# dsau-micro-zed.net
KiCad netlist of a schematic drawn in Altium Designer
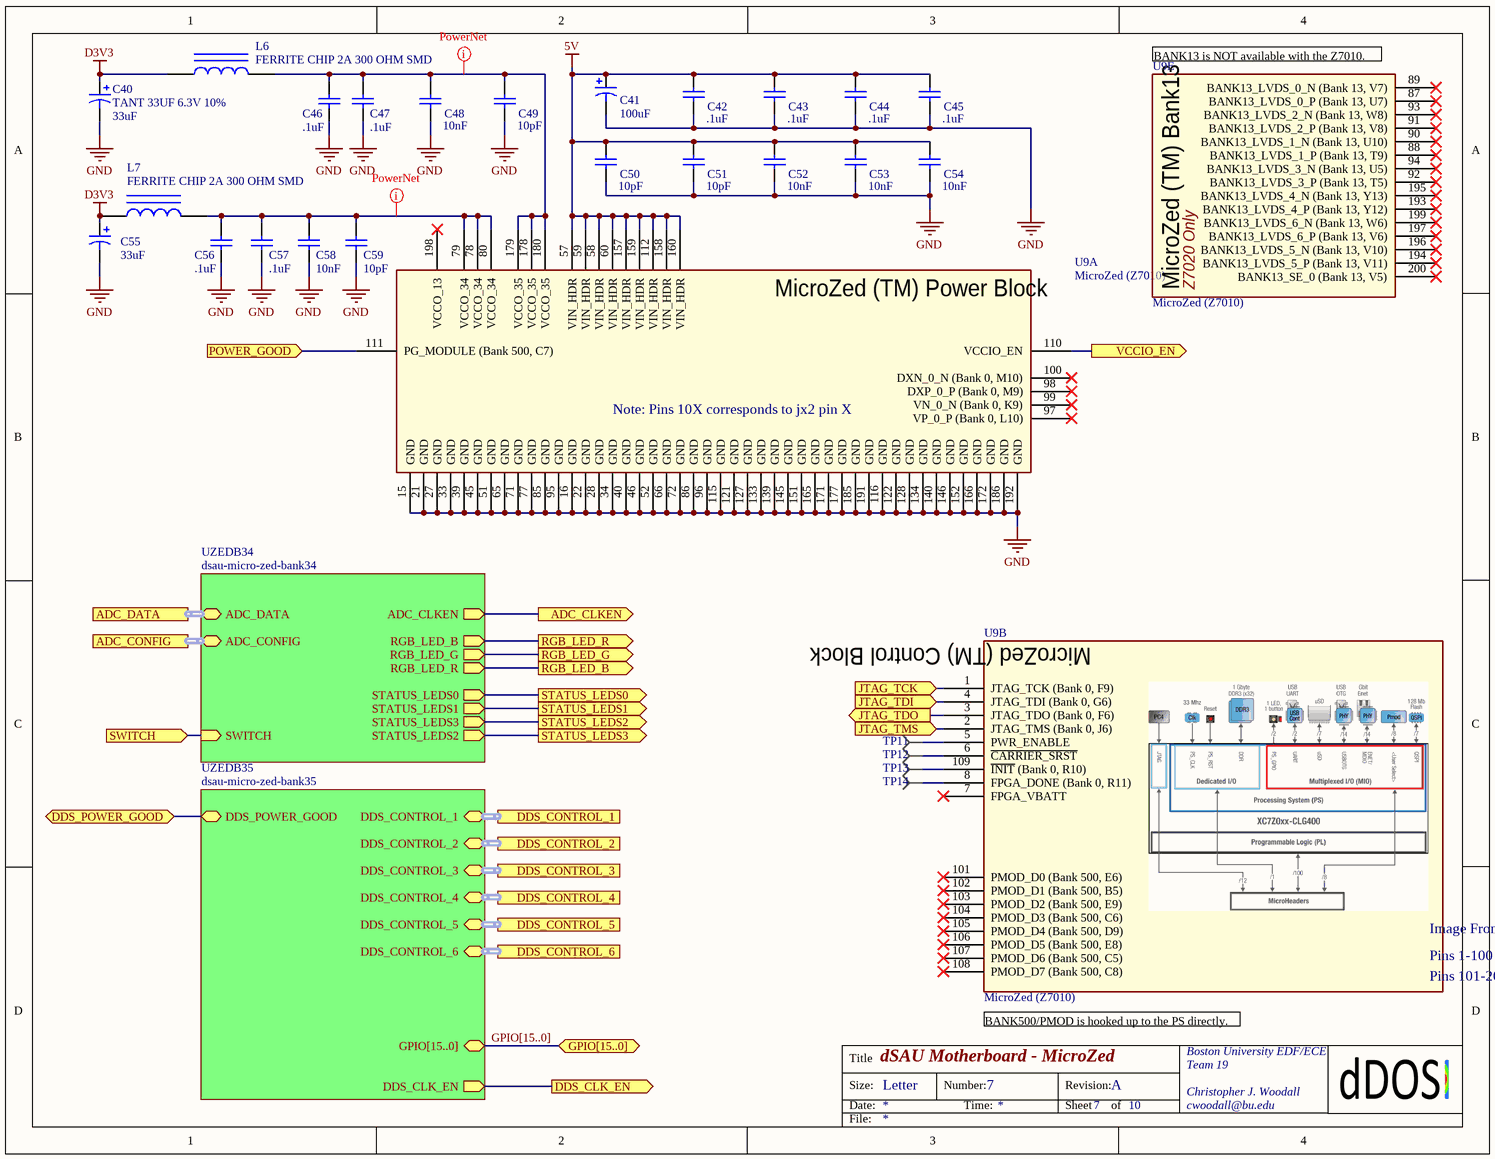
[diagram p0: dsau-micro-zed.SchDoc]

(export (version "E")
  (design (tool "Eeschema 10.0.6"))
  (components
    (comp (ref "C40")
      (value "TANT 33UF 6.3V 10%")
      (footprint "CAPC2012L")
      (description "Polarized Capacitor (Surface Mount)")
      (fields
        (field (name "ALTIUM_VALUE") "33uF")
        (field (name "MANUFACTURER") "AVX Corporation")
        (field (name "MANUFACTURER PART NUMBER") "TPSA336K006R0600")
        (field (name "PUBLISHER") "Altium Limited")
      )
      (libsource (lib "") (part "Cap Pol3_1"))
    )
    (comp (ref "C41")
      (value "100uF")
      (footprint "CAPPOL3216")
      (description "Polarized Capacitor (Surface Mount)")
      (fields
        (field (name "MANUFACTURER") "Vishay Sprague")
        (field (name "MANUFACTURER PART NUMBER") "TL8A0107M010C")
        (field (name "PUBLISHER") "Altium Limited")
      )
      (libsource (lib "Miscellaneous Devices") (part "Cap Pol3"))
    )
    (comp (ref "C42")
      (value ".1uF")
      (footprint "CAPC1608L")
      (description "Capacitor")
      (fields
        (field (name "MANUFACTURER") "Yageo")
        (field (name "MANUFACTURER PART NUMBER") "CC0603ZRY5V9BB104")
        (field (name "PUBLISHER") "Altium Limited")
      )
      (libsource (lib "Miscellaneous Devices") (part "Cap"))
    )
    (comp (ref "C43")
      (value ".1uF")
      (footprint "CAPC1608L")
      (description "Capacitor")
      (fields
        (field (name "MANUFACTURER") "Yageo")
        (field (name "MANUFACTURER PART NUMBER") "CC0603ZRY5V9BB104")
        (field (name "PUBLISHER") "Altium Limited")
      )
      (libsource (lib "Miscellaneous Devices") (part "Cap"))
    )
    (comp (ref "C44")
      (value ".1uF")
      (footprint "CAPC1608L")
      (description "Capacitor")
      (fields
        (field (name "MANUFACTURER") "Yageo")
        (field (name "MANUFACTURER PART NUMBER") "CC0603ZRY5V9BB104")
        (field (name "PUBLISHER") "Altium Limited")
      )
      (libsource (lib "Miscellaneous Devices") (part "Cap"))
    )
    (comp (ref "C45")
      (value ".1uF")
      (footprint "CAPC1608L")
      (description "Capacitor")
      (fields
        (field (name "MANUFACTURER") "Yageo")
        (field (name "MANUFACTURER PART NUMBER") "CC0603ZRY5V9BB104")
        (field (name "PUBLISHER") "Altium Limited")
      )
      (libsource (lib "Miscellaneous Devices") (part "Cap"))
    )
    (comp (ref "C46")
      (value ".1uF")
      (footprint "CAPC1608L")
      (description "Capacitor")
      (fields
        (field (name "MANUFACTURER") "Yageo")
        (field (name "MANUFACTURER PART NUMBER") "CC0603ZRY5V9BB104")
        (field (name "PUBLISHER") "Altium Limited")
      )
      (libsource (lib "Miscellaneous Devices") (part "Cap"))
    )
    (comp (ref "C47")
      (value ".1uF")
      (footprint "CAPC1608L")
      (description "Capacitor")
      (fields
        (field (name "MANUFACTURER") "Yageo")
        (field (name "MANUFACTURER PART NUMBER") "CC0603ZRY5V9BB104")
        (field (name "PUBLISHER") "Altium Limited")
      )
      (libsource (lib "Miscellaneous Devices") (part "Cap"))
    )
    (comp (ref "C48")
      (value "10nF")
      (footprint "CAPC1608L")
      (description "Capacitor")
      (fields
        (field (name "MANUFACTURER") "Kemet")
        (field (name "MANUFACTURER PART NUMBER") "C0603C103K3GACTU")
        (field (name "PUBLISHER") "Altium Limited")
      )
      (libsource (lib "Miscellaneous Devices") (part "Cap"))
    )
    (comp (ref "C49")
      (value "10pF")
      (footprint "CAPC1608L")
      (description "Capacitor")
      (fields
        (field (name "MANUFACTURER") "Samsung Electro-Mechanics America, Inc")
        (field (name "MANUFACTURER PART NUMBER") "CL10C100JB8NCNC")
        (field (name "PUBLISHER") "Altium Limited")
      )
      (libsource (lib "Miscellaneous Devices") (part "Cap"))
    )
    (comp (ref "C50")
      (value "10pF")
      (footprint "CAPC1608L")
      (description "Capacitor")
      (fields
        (field (name "MANUFACTURER") "Samsung Electro-Mechanics America, Inc")
        (field (name "MANUFACTURER PART NUMBER") "CL10C100JB8NCNC")
        (field (name "PUBLISHER") "Altium Limited")
      )
      (libsource (lib "Miscellaneous Devices") (part "Cap"))
    )
    (comp (ref "C51")
      (value "10pF")
      (footprint "CAPC1608L")
      (description "Capacitor")
      (fields
        (field (name "MANUFACTURER") "Samsung Electro-Mechanics America, Inc")
        (field (name "MANUFACTURER PART NUMBER") "CL10C100JB8NCNC")
        (field (name "PUBLISHER") "Altium Limited")
      )
      (libsource (lib "Miscellaneous Devices") (part "Cap"))
    )
    (comp (ref "C52")
      (value "10nF")
      (footprint "CAPC1608L")
      (description "Capacitor")
      (fields
        (field (name "MANUFACTURER") "Kemet")
        (field (name "MANUFACTURER PART NUMBER") "C0603C103K3GACTU")
        (field (name "PUBLISHER") "Altium Limited")
      )
      (libsource (lib "Miscellaneous Devices") (part "Cap"))
    )
    (comp (ref "C53")
      (value "10nF")
      (footprint "CAPC1608L")
      (description "Capacitor")
      (fields
        (field (name "MANUFACTURER") "Kemet")
        (field (name "MANUFACTURER PART NUMBER") "C0603C103K3GACTU")
        (field (name "PUBLISHER") "Altium Limited")
      )
      (libsource (lib "Miscellaneous Devices") (part "Cap"))
    )
    (comp (ref "C54")
      (value "10nF")
      (footprint "CAPC1608L")
      (description "Capacitor")
      (fields
        (field (name "MANUFACTURER") "Kemet")
        (field (name "MANUFACTURER PART NUMBER") "C0603C103K3GACTU")
        (field (name "PUBLISHER") "Altium Limited")
      )
      (libsource (lib "Miscellaneous Devices") (part "Cap"))
    )
    (comp (ref "C55")
      (value "33uF")
      (footprint "CAPC2012L")
      (description "Polarized Capacitor (Surface Mount)")
      (fields
        (field (name "MANUFACTURER") "AVX Corporation")
        (field (name "MANUFACTURER PART NUMBER") "TPSA336K006R0600")
        (field (name "PUBLISHER") "Altium Limited")
      )
      (libsource (lib "") (part "Cap Pol3_1"))
    )
    (comp (ref "C56")
      (value ".1uF")
      (footprint "CAPC1608L")
      (description "Capacitor")
      (fields
        (field (name "MANUFACTURER") "Yageo")
        (field (name "MANUFACTURER PART NUMBER") "CC0603ZRY5V9BB104")
        (field (name "PUBLISHER") "Altium Limited")
      )
      (libsource (lib "Miscellaneous Devices") (part "Cap"))
    )
    (comp (ref "C57")
      (value ".1uF")
      (footprint "CAPC1608L")
      (description "Capacitor")
      (fields
        (field (name "MANUFACTURER") "Yageo")
        (field (name "MANUFACTURER PART NUMBER") "CC0603ZRY5V9BB104")
        (field (name "PUBLISHER") "Altium Limited")
      )
      (libsource (lib "Miscellaneous Devices") (part "Cap"))
    )
    (comp (ref "C58")
      (value "10nF")
      (footprint "CAPC1608L")
      (description "Capacitor")
      (fields
        (field (name "MANUFACTURER") "Kemet")
        (field (name "MANUFACTURER PART NUMBER") "C0603C103K3GACTU")
        (field (name "PUBLISHER") "Altium Limited")
      )
      (libsource (lib "Miscellaneous Devices") (part "Cap"))
    )
    (comp (ref "C59")
      (value "10pF")
      (footprint "CAPC1608L")
      (description "Capacitor")
      (fields
        (field (name "MANUFACTURER") "Samsung Electro-Mechanics America, Inc")
        (field (name "MANUFACTURER PART NUMBER") "CL10C100JB8NCNC")
        (field (name "PUBLISHER") "Altium Limited")
      )
      (libsource (lib "Miscellaneous Devices") (part "Cap"))
    )
    (comp (ref "L6")
      (value "FERRITE CHIP 2A 300 OHM SMD")
      (footprint "INDC1608L")
      (description "Magnetic-Core Inductor")
      (fields
        (field (name "MANUFACTURER") "Laird-Signal Integrity Products")
        (field (name "MANUFACTURER PART NUMBER") "MI0603L301R-10")
        (field (name "PUBLISHER") "Altium Limited")
      )
      (libsource (lib "Miscellaneous Devices") (part "Inductor Iron"))
    )
    (comp (ref "L7")
      (value "FERRITE CHIP 2A 300 OHM SMD")
      (footprint "INDC1608L")
      (description "Magnetic-Core Inductor")
      (fields
        (field (name "MANUFACTURER") "Laird-Signal Integrity Products")
        (field (name "MANUFACTURER PART NUMBER") "MI0603L301R-10")
        (field (name "PUBLISHER") "Altium Limited")
      )
      (libsource (lib "Miscellaneous Devices") (part "Inductor Iron"))
    )
    (comp (ref "TP11")
      (value "TESTPOINT_CW")
      (footprint "PIN1")
      (fields (field (name "MANUFACTURER") "Keystone") (field (name "MANUFACTURER PART NUMBER") "5000"))
      (libsource (lib "dsau-motherboard") (part "TESTPOINT_CW"))
    )
    (comp (ref "TP12")
      (value "TESTPOINT_CW")
      (footprint "PIN1")
      (fields (field (name "MANUFACTURER") "Keystone") (field (name "MANUFACTURER PART NUMBER") "5000"))
      (libsource (lib "dsau-motherboard") (part "TESTPOINT_CW"))
    )
    (comp (ref "TP13")
      (value "TESTPOINT_CW")
      (footprint "PIN1")
      (fields (field (name "MANUFACTURER") "Keystone") (field (name "MANUFACTURER PART NUMBER") "5000"))
      (libsource (lib "dsau-motherboard") (part "TESTPOINT_CW"))
    )
    (comp (ref "TP14")
      (value "TESTPOINT_CW")
      (footprint "PIN1")
      (fields (field (name "MANUFACTURER") "Keystone") (field (name "MANUFACTURER PART NUMBER") "5000"))
      (libsource (lib "dsau-motherboard") (part "TESTPOINT_CW"))
    )
    (comp (ref "U9")
      (value "MicroZed (Z7010)")
      (footprint "MicroZed_MatingSide")
      (fields
        (field (name "MANUFACTURER") "Avnet")
        (field (name "MANFACTURER PART NUMBER") "AES-Z7MB-7Z010-G")
      )
      (libsource (lib "dsau-motherboard") (part "MicroZed"))
    )
  )
  (nets
    (net (code "37") (name "/JTAG_TCK") (class "Default")
      (node (ref "U9") (pin "1") (pinfunction "JTAG_TCK_(Bank_0,_F9)_1") (pintype "passive"))
    )
    (net (code "38") (name "/JTAG_TDI") (class "Default")
      (node (ref "U9") (pin "4") (pinfunction "JTAG_TDI_(Bank_0,_G6)_4") (pintype "passive"))
    )
    (net (code "39") (name "/JTAG_TDO") (class "Default")
      (node (ref "U9") (pin "3") (pinfunction "JTAG_TDO_(Bank_0,_F6)_3") (pintype "passive"))
    )
    (net (code "40") (name "/JTAG_TMS") (class "Default")
      (node (ref "U9") (pin "2") (pinfunction "JTAG_TMS_(Bank_0,_J6)_2") (pintype "passive"))
    )
    (net (code "41") (name "/POWER_GOOD") (class "Default")
      (node (ref "U9") (pin "111") (pinfunction "PG_MODULE_(Bank_500,_C7)_111") (pintype "passive"))
    )
    (net (code "50") (name "/VCCIO_EN") (class "Default")
      (node (ref "U9") (pin "110") (pinfunction "VCCIO_EN_110") (pintype "passive"))
    )
    (net (code "51") (name "5V") (class "Default")
      (node (ref "C41") (pin "1") (pinfunction "1_1") (pintype "passive"))
      (node (ref "C42") (pin "1") (pinfunction "1_1") (pintype "passive"))
      (node (ref "C43") (pin "1") (pinfunction "1_1") (pintype "passive"))
      (node (ref "C44") (pin "1") (pinfunction "1_1") (pintype "passive"))
      (node (ref "C45") (pin "1") (pinfunction "1_1") (pintype "passive"))
      (node (ref "C50") (pin "1") (pinfunction "1_1") (pintype "passive"))
      (node (ref "C51") (pin "1") (pinfunction "1_1") (pintype "passive"))
      (node (ref "C52") (pin "1") (pinfunction "1_1") (pintype "passive"))
      (node (ref "C53") (pin "1") (pinfunction "1_1") (pintype "passive"))
      (node (ref "C54") (pin "1") (pinfunction "1_1") (pintype "passive"))
      (node (ref "U9") (pin "112") (pinfunction "VIN_HDR_112") (pintype "power_in"))
      (node (ref "U9") (pin "157") (pinfunction "VIN_HDR_157") (pintype "power_in"))
      (node (ref "U9") (pin "158") (pinfunction "VIN_HDR_158") (pintype "power_in"))
      (node (ref "U9") (pin "159") (pinfunction "VIN_HDR_159") (pintype "power_in"))
      (node (ref "U9") (pin "160") (pinfunction "VIN_HDR_160") (pintype "power_in"))
      (node (ref "U9") (pin "57") (pinfunction "VIN_HDR_57") (pintype "power_in"))
      (node (ref "U9") (pin "58") (pinfunction "VIN_HDR_58") (pintype "power_in"))
      (node (ref "U9") (pin "59") (pinfunction "VIN_HDR_59") (pintype "power_in"))
      (node (ref "U9") (pin "60") (pinfunction "VIN_HDR_60") (pintype "power_in"))
    )
    (net (code "52") (name "D3V3") (class "Default")
      (node (ref "C40") (pin "1") (pinfunction "1_1") (pintype "passive"))
      (node (ref "C55") (pin "1") (pinfunction "1_1") (pintype "passive"))
      (node (ref "L6") (pin "1") (pinfunction "1_1") (pintype "passive"))
      (node (ref "L7") (pin "1") (pinfunction "1_1") (pintype "passive"))
    )
    (net (code "53") (name "GND") (class "Default")
      (node (ref "C40") (pin "2") (pinfunction "2_2") (pintype "passive"))
      (node (ref "C41") (pin "2") (pinfunction "2_2") (pintype "passive"))
      (node (ref "C42") (pin "2") (pinfunction "2_2") (pintype "passive"))
      (node (ref "C43") (pin "2") (pinfunction "2_2") (pintype "passive"))
      (node (ref "C44") (pin "2") (pinfunction "2_2") (pintype "passive"))
      (node (ref "C45") (pin "2") (pinfunction "2_2") (pintype "passive"))
      (node (ref "C46") (pin "2") (pinfunction "2_2") (pintype "passive"))
      (node (ref "C47") (pin "2") (pinfunction "2_2") (pintype "passive"))
      (node (ref "C48") (pin "2") (pinfunction "2_2") (pintype "passive"))
      (node (ref "C49") (pin "2") (pinfunction "2_2") (pintype "passive"))
      (node (ref "C50") (pin "2") (pinfunction "2_2") (pintype "passive"))
      (node (ref "C51") (pin "2") (pinfunction "2_2") (pintype "passive"))
      (node (ref "C52") (pin "2") (pinfunction "2_2") (pintype "passive"))
      (node (ref "C53") (pin "2") (pinfunction "2_2") (pintype "passive"))
      (node (ref "C54") (pin "2") (pinfunction "2_2") (pintype "passive"))
      (node (ref "C55") (pin "2") (pinfunction "2_2") (pintype "passive"))
      (node (ref "C56") (pin "2") (pinfunction "2_2") (pintype "passive"))
      (node (ref "C57") (pin "2") (pinfunction "2_2") (pintype "passive"))
      (node (ref "C58") (pin "2") (pinfunction "2_2") (pintype "passive"))
      (node (ref "C59") (pin "2") (pinfunction "2_2") (pintype "passive"))
      (node (ref "U9") (pin "115") (pinfunction "GND_115") (pintype "power_in"))
      (node (ref "U9") (pin "116") (pinfunction "GND_116") (pintype "power_in"))
      (node (ref "U9") (pin "121") (pinfunction "GND_121") (pintype "power_in"))
      (node (ref "U9") (pin "122") (pinfunction "GND_122") (pintype "power_in"))
      (node (ref "U9") (pin "127") (pinfunction "GND_127") (pintype "power_in"))
      (node (ref "U9") (pin "128") (pinfunction "GND_128") (pintype "power_in"))
      (node (ref "U9") (pin "133") (pinfunction "GND_133") (pintype "power_in"))
      (node (ref "U9") (pin "134") (pinfunction "GND_134") (pintype "power_in"))
      (node (ref "U9") (pin "139") (pinfunction "GND_139") (pintype "power_in"))
      (node (ref "U9") (pin "140") (pinfunction "GND_140") (pintype "power_in"))
      (node (ref "U9") (pin "145") (pinfunction "GND_145") (pintype "power_in"))
      (node (ref "U9") (pin "146") (pinfunction "GND_146") (pintype "power_in"))
      (node (ref "U9") (pin "15") (pinfunction "GND_15") (pintype "power_in"))
      (node (ref "U9") (pin "151") (pinfunction "GND_151") (pintype "power_in"))
      (node (ref "U9") (pin "152") (pinfunction "GND_152") (pintype "power_in"))
      (node (ref "U9") (pin "16") (pinfunction "GND_16") (pintype "power_in"))
      (node (ref "U9") (pin "165") (pinfunction "GND_165") (pintype "power_in"))
      (node (ref "U9") (pin "166") (pinfunction "GND_166") (pintype "power_in"))
      (node (ref "U9") (pin "171") (pinfunction "GND_171") (pintype "power_in"))
      (node (ref "U9") (pin "172") (pinfunction "GND_172") (pintype "power_in"))
      (node (ref "U9") (pin "177") (pinfunction "GND_177") (pintype "power_in"))
      (node (ref "U9") (pin "185") (pinfunction "GND_185") (pintype "power_in"))
      (node (ref "U9") (pin "186") (pinfunction "GND_186") (pintype "power_in"))
      (node (ref "U9") (pin "191") (pinfunction "GND_191") (pintype "power_in"))
      (node (ref "U9") (pin "192") (pinfunction "GND_192") (pintype "power_in"))
      (node (ref "U9") (pin "21") (pinfunction "GND_21") (pintype "power_in"))
      (node (ref "U9") (pin "22") (pinfunction "GND_22") (pintype "power_in"))
      (node (ref "U9") (pin "27") (pinfunction "GND_27") (pintype "power_in"))
      (node (ref "U9") (pin "28") (pinfunction "GND_28") (pintype "power_in"))
      (node (ref "U9") (pin "33") (pinfunction "GND_33") (pintype "power_in"))
      (node (ref "U9") (pin "34") (pinfunction "GND_34") (pintype "power_in"))
      (node (ref "U9") (pin "39") (pinfunction "GND_39") (pintype "power_in"))
      (node (ref "U9") (pin "40") (pinfunction "GND_40") (pintype "power_in"))
      (node (ref "U9") (pin "45") (pinfunction "GND_45") (pintype "power_in"))
      (node (ref "U9") (pin "46") (pinfunction "GND_46") (pintype "power_in"))
      (node (ref "U9") (pin "51") (pinfunction "GND_51") (pintype "power_in"))
      (node (ref "U9") (pin "52") (pinfunction "GND_52") (pintype "power_in"))
      (node (ref "U9") (pin "65") (pinfunction "GND_65") (pintype "power_in"))
      (node (ref "U9") (pin "66") (pinfunction "GND_66") (pintype "power_in"))
      (node (ref "U9") (pin "71") (pinfunction "GND_71") (pintype "power_in"))
      (node (ref "U9") (pin "72") (pinfunction "GND_72") (pintype "power_in"))
      (node (ref "U9") (pin "77") (pinfunction "GND_77") (pintype "power_in"))
      (node (ref "U9") (pin "85") (pinfunction "GND_85") (pintype "power_in"))
      (node (ref "U9") (pin "86") (pinfunction "GND_86") (pintype "power_in"))
      (node (ref "U9") (pin "95") (pinfunction "GND_95") (pintype "power_in"))
      (node (ref "U9") (pin "96") (pinfunction "GND_96") (pintype "power_in"))
    )
    (net (code "54") (name "Net-(C46-Pad1)") (class "Default")
      (node (ref "C46") (pin "1") (pinfunction "1_1") (pintype "passive"))
      (node (ref "C47") (pin "1") (pinfunction "1_1") (pintype "passive"))
      (node (ref "C48") (pin "1") (pinfunction "1_1") (pintype "passive"))
      (node (ref "C49") (pin "1") (pinfunction "1_1") (pintype "passive"))
      (node (ref "L6") (pin "2") (pinfunction "2_2") (pintype "passive"))
      (node (ref "U9") (pin "178") (pinfunction "VCCO_35_178") (pintype "power_in"))
      (node (ref "U9") (pin "179") (pinfunction "VCCO_35_179") (pintype "power_in"))
      (node (ref "U9") (pin "180") (pinfunction "VCCO_35_180") (pintype "power_in"))
    )
    (net (code "55") (name "Net-(C56-Pad1)") (class "Default")
      (node (ref "C56") (pin "1") (pinfunction "1_1") (pintype "passive"))
      (node (ref "C57") (pin "1") (pinfunction "1_1") (pintype "passive"))
      (node (ref "C58") (pin "1") (pinfunction "1_1") (pintype "passive"))
      (node (ref "C59") (pin "1") (pinfunction "1_1") (pintype "passive"))
      (node (ref "L7") (pin "2") (pinfunction "2_2") (pintype "passive"))
      (node (ref "U9") (pin "78") (pinfunction "VCCO_34_78") (pintype "power_in"))
      (node (ref "U9") (pin "79") (pinfunction "VCCO_34_79") (pintype "power_in"))
      (node (ref "U9") (pin "80") (pinfunction "VCCO_34_80") (pintype "power_in"))
    )
    (net (code "56") (name "Net-(U9B-FPGA_DONE_(Bank_0,_R11))") (class "Default")
      (node (ref "TP14") (pin "1") (pintype "passive"))
      (node (ref "U9") (pin "8") (pinfunction "FPGA_DONE_(Bank_0,_R11)_8") (pintype "passive"))
    )
    (net (code "57") (name "Net-(U9B-PWR_ENABLE)") (class "Default")
      (node (ref "TP11") (pin "1") (pintype "passive"))
      (node (ref "U9") (pin "5") (pinfunction "PWR_ENABLE_5") (pintype "passive"))
    )
    (net (code "58") (name "Net-(U9B-~{CARRIER_SRST})") (class "Default")
      (node (ref "TP12") (pin "1") (pintype "passive"))
      (node (ref "U9") (pin "6") (pinfunction "~{CARRIER_SRST}_6") (pintype "passive"))
    )
    (net (code "59") (name "Net-(U9B-~{INIT}_(Bank_0,_R10))") (class "Default")
      (node (ref "TP13") (pin "1") (pintype "passive"))
      (node (ref "U9") (pin "109") (pinfunction "~{INIT}_(Bank_0,_R10)_109") (pintype "passive"))
    )
    (net (code "60") (name "unconnected-(U9A-DXN_0_N_(Bank_0,_M10)-Pad100)") (class "Default")
      (node (ref "U9") (pin "100") (pinfunction "DXN_0_N_(Bank_0,_M10)_100") (pintype "passive+no_connect"))
    )
    (net (code "61") (name "unconnected-(U9A-DXP_0_P_(Bank_0,_M9)-Pad98)") (class "Default")
      (node (ref "U9") (pin "98") (pinfunction "DXP_0_P_(Bank_0,_M9)_98") (pintype "passive+no_connect"))
    )
    (net (code "62") (name "unconnected-(U9A-VCCO_13-Pad198)") (class "Default")
      (node (ref "U9") (pin "198") (pinfunction "VCCO_13_198") (pintype "power_in+no_connect"))
    )
    (net (code "63") (name "unconnected-(U9A-VN_0_N_(Bank_0,_K9)-Pad99)") (class "Default")
      (node (ref "U9") (pin "99") (pinfunction "VN_0_N_(Bank_0,_K9)_99") (pintype "passive+no_connect"))
    )
    (net (code "64") (name "unconnected-(U9A-VP_0_P_(Bank_0,_L10)-Pad97)") (class "Default")
      (node (ref "U9") (pin "97") (pinfunction "VP_0_P_(Bank_0,_L10)_97") (pintype "passive+no_connect"))
    )
    (net (code "65") (name "unconnected-(U9B-FPGA_VBATT-Pad7)") (class "Default")
      (node (ref "U9") (pin "7") (pinfunction "FPGA_VBATT_7") (pintype "passive+no_connect"))
    )
    (net (code "66") (name "unconnected-(U9B-PMOD_D0_(Bank_500,_E6)-Pad101)") (class "Default")
      (node (ref "U9") (pin "101") (pinfunction "PMOD_D0_(Bank_500,_E6)_101") (pintype "passive+no_connect"))
    )
    (net (code "67") (name "unconnected-(U9B-PMOD_D1_(Bank_500,_B5)-Pad102)") (class "Default")
      (node (ref "U9") (pin "102") (pinfunction "PMOD_D1_(Bank_500,_B5)_102") (pintype "passive+no_connect"))
    )
    (net (code "68") (name "unconnected-(U9B-PMOD_D2_(Bank_500,_E9)-Pad103)") (class "Default")
      (node (ref "U9") (pin "103") (pinfunction "PMOD_D2_(Bank_500,_E9)_103") (pintype "passive+no_connect"))
    )
    (net (code "69") (name "unconnected-(U9B-PMOD_D3_(Bank_500,_C6)-Pad104)") (class "Default")
      (node (ref "U9") (pin "104") (pinfunction "PMOD_D3_(Bank_500,_C6)_104") (pintype "passive+no_connect"))
    )
    (net (code "70") (name "unconnected-(U9B-PMOD_D4_(Bank_500,_D9)-Pad105)") (class "Default")
      (node (ref "U9") (pin "105") (pinfunction "PMOD_D4_(Bank_500,_D9)_105") (pintype "passive+no_connect"))
    )
    (net (code "71") (name "unconnected-(U9B-PMOD_D5_(Bank_500,_E8)-Pad106)") (class "Default")
      (node (ref "U9") (pin "106") (pinfunction "PMOD_D5_(Bank_500,_E8)_106") (pintype "passive+no_connect"))
    )
    (net (code "72") (name "unconnected-(U9B-PMOD_D6_(Bank_500,_C5)-Pad107)") (class "Default")
      (node (ref "U9") (pin "107") (pinfunction "PMOD_D6_(Bank_500,_C5)_107") (pintype "passive+no_connect"))
    )
    (net (code "73") (name "unconnected-(U9B-PMOD_D7_(Bank_500,_C8)-Pad108)") (class "Default")
      (node (ref "U9") (pin "108") (pinfunction "PMOD_D7_(Bank_500,_C8)_108") (pintype "passive+no_connect"))
    )
    (net (code "74") (name "unconnected-(U9E-BANK13_LVDS_0_N_(Bank_13,_V7)-Pad89)") (class "Default")
      (node (ref "U9") (pin "89") (pinfunction "BANK13_LVDS_0_N_(Bank_13,_V7)_89") (pintype "passive+no_connect"))
    )
    (net (code "75") (name "unconnected-(U9E-BANK13_LVDS_0_P_(Bank_13,_U7)-Pad87)") (class "Default")
      (node (ref "U9") (pin "87") (pinfunction "BANK13_LVDS_0_P_(Bank_13,_U7)_87") (pintype "passive+no_connect"))
    )
    (net (code "76") (name "unconnected-(U9E-BANK13_LVDS_1_N_(Bank_13,_U10)-Pad90)") (class "Default")
      (node (ref "U9") (pin "90") (pinfunction "BANK13_LVDS_1_N_(Bank_13,_U10)_90") (pintype "passive+no_connect"))
    )
    (net (code "77") (name "unconnected-(U9E-BANK13_LVDS_1_P_(Bank_13,_T9)-Pad88)") (class "Default")
      (node (ref "U9") (pin "88") (pinfunction "BANK13_LVDS_1_P_(Bank_13,_T9)_88") (pintype "passive+no_connect"))
    )
    (net (code "78") (name "unconnected-(U9E-BANK13_LVDS_2_N_(Bank_13,_W8)-Pad93)") (class "Default")
      (node (ref "U9") (pin "93") (pinfunction "BANK13_LVDS_2_N_(Bank_13,_W8)_93") (pintype "passive+no_connect"))
    )
    (net (code "79") (name "unconnected-(U9E-BANK13_LVDS_2_P_(Bank_13,_V8)-Pad91)") (class "Default")
      (node (ref "U9") (pin "91") (pinfunction "BANK13_LVDS_2_P_(Bank_13,_V8)_91") (pintype "passive+no_connect"))
    )
    (net (code "80") (name "unconnected-(U9E-BANK13_LVDS_3_N_(Bank_13,_U5)-Pad94)") (class "Default")
      (node (ref "U9") (pin "94") (pinfunction "BANK13_LVDS_3_N_(Bank_13,_U5)_94") (pintype "passive+no_connect"))
    )
    (net (code "81") (name "unconnected-(U9E-BANK13_LVDS_3_P_(Bank_13,_T5)-Pad92)") (class "Default")
      (node (ref "U9") (pin "92") (pinfunction "BANK13_LVDS_3_P_(Bank_13,_T5)_92") (pintype "passive+no_connect"))
    )
    (net (code "82") (name "unconnected-(U9E-BANK13_LVDS_4_N_(Bank_13,_Y13)-Pad195)") (class "Default")
      (node (ref "U9") (pin "195") (pinfunction "BANK13_LVDS_4_N_(Bank_13,_Y13)_195") (pintype "passive+no_connect"))
    )
    (net (code "83") (name "unconnected-(U9E-BANK13_LVDS_4_P_(Bank_13,_Y12)-Pad193)") (class "Default")
      (node (ref "U9") (pin "193") (pinfunction "BANK13_LVDS_4_P_(Bank_13,_Y12)_193") (pintype "passive+no_connect"))
    )
    (net (code "84") (name "unconnected-(U9E-BANK13_LVDS_5_N_(Bank_13,_V10)-Pad196)") (class "Default")
      (node (ref "U9") (pin "196") (pinfunction "BANK13_LVDS_5_N_(Bank_13,_V10)_196") (pintype "passive+no_connect"))
    )
    (net (code "85") (name "unconnected-(U9E-BANK13_LVDS_5_P_(Bank_13,_V11)-Pad194)") (class "Default")
      (node (ref "U9") (pin "194") (pinfunction "BANK13_LVDS_5_P_(Bank_13,_V11)_194") (pintype "passive+no_connect"))
    )
    (net (code "86") (name "unconnected-(U9E-BANK13_LVDS_6_N_(Bank_13,_W6)-Pad199)") (class "Default")
      (node (ref "U9") (pin "199") (pinfunction "BANK13_LVDS_6_N_(Bank_13,_W6)_199") (pintype "passive+no_connect"))
    )
    (net (code "87") (name "unconnected-(U9E-BANK13_LVDS_6_P_(Bank_13,_V6)-Pad197)") (class "Default")
      (node (ref "U9") (pin "197") (pinfunction "BANK13_LVDS_6_P_(Bank_13,_V6)_197") (pintype "passive+no_connect"))
    )
    (net (code "88") (name "unconnected-(U9E-BANK13_SE_0_(Bank_13,_V5)-Pad200)") (class "Default")
      (node (ref "U9") (pin "200") (pinfunction "BANK13_SE_0_(Bank_13,_V5)_200") (pintype "passive+no_connect"))
    )
  )
)
